# sensor-input.net
KiCad netlist of a schematic drawn in EAGLE
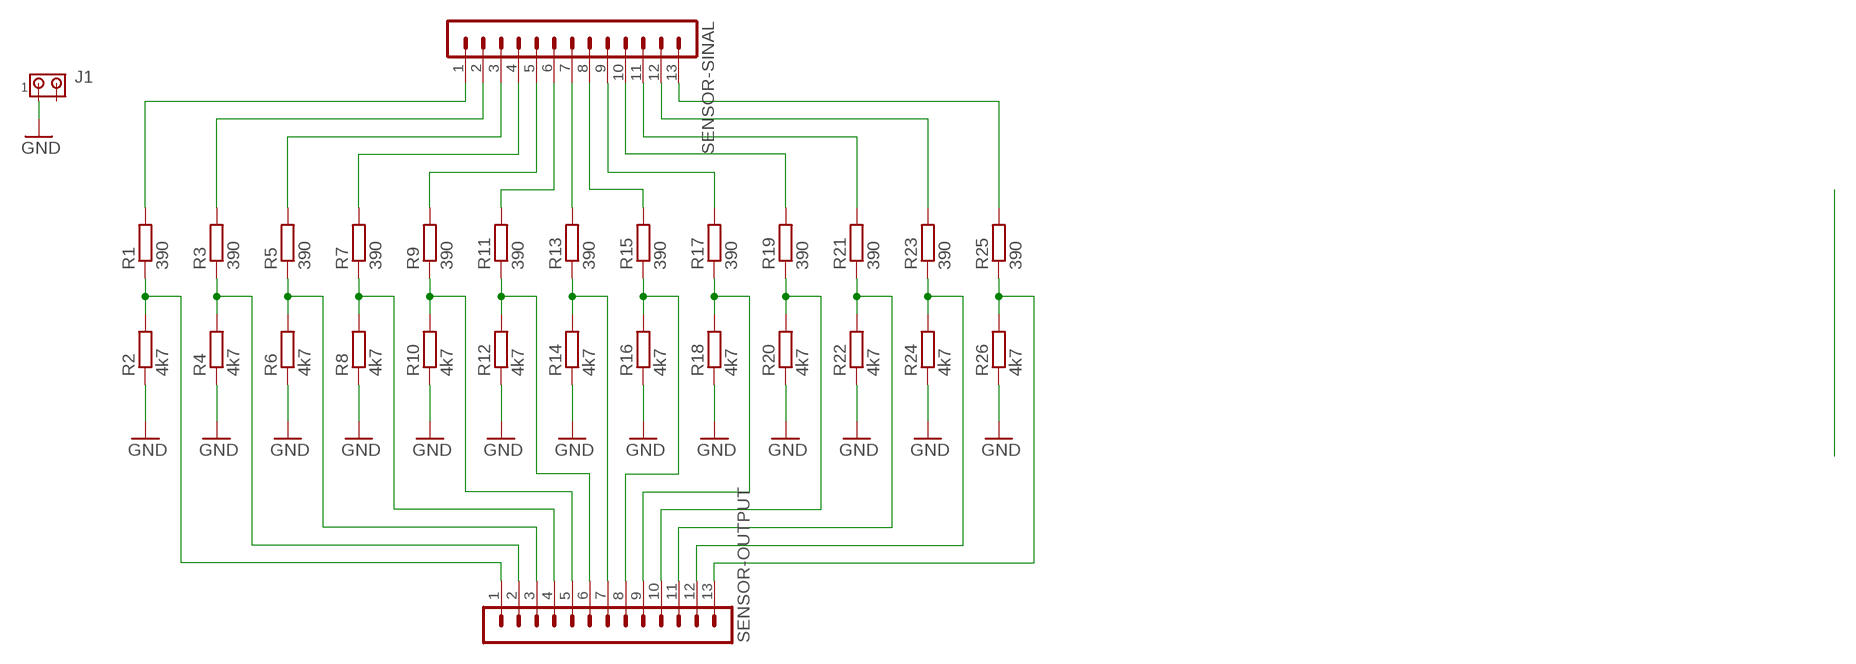
[diagram p0: schematic, sheet 1]

(export (version "E")
  (design (tool "Eeschema 10.0.6"))
  (components
    (comp (ref "J1")
      (value "MTA02-100")
      (footprint "eagle-import:10X02MTA")
      (libsource (lib "eagle-import") (part "MTA02-100"))
    )
    (comp (ref "R1")
      (value "390")
      (footprint "eagle-import:0207_7")
      (libsource (lib "eagle-import") (part "R-EU_0207/7"))
    )
    (comp (ref "R2")
      (value "4k7")
      (footprint "eagle-import:0207_7")
      (libsource (lib "eagle-import") (part "R-EU_0207/7"))
    )
    (comp (ref "R3")
      (value "390")
      (footprint "eagle-import:0207_7")
      (libsource (lib "eagle-import") (part "R-EU_0207/7"))
    )
    (comp (ref "R4")
      (value "4k7")
      (footprint "eagle-import:0207_7")
      (libsource (lib "eagle-import") (part "R-EU_0207/7"))
    )
    (comp (ref "R5")
      (value "390")
      (footprint "eagle-import:0207_7")
      (libsource (lib "eagle-import") (part "R-EU_0207/7"))
    )
    (comp (ref "R6")
      (value "4k7")
      (footprint "eagle-import:0207_7")
      (libsource (lib "eagle-import") (part "R-EU_0207/7"))
    )
    (comp (ref "R7")
      (value "390")
      (footprint "eagle-import:0207_7")
      (libsource (lib "eagle-import") (part "R-EU_0207/7"))
    )
    (comp (ref "R8")
      (value "4k7")
      (footprint "eagle-import:0207_7")
      (libsource (lib "eagle-import") (part "R-EU_0207/7"))
    )
    (comp (ref "R9")
      (value "390")
      (footprint "eagle-import:0207_7")
      (libsource (lib "eagle-import") (part "R-EU_0207/7"))
    )
    (comp (ref "R10")
      (value "4k7")
      (footprint "eagle-import:0207_7")
      (libsource (lib "eagle-import") (part "R-EU_0207/7"))
    )
    (comp (ref "R11")
      (value "390")
      (footprint "eagle-import:0207_7")
      (libsource (lib "eagle-import") (part "R-EU_0207/7"))
    )
    (comp (ref "R12")
      (value "4k7")
      (footprint "eagle-import:0207_7")
      (libsource (lib "eagle-import") (part "R-EU_0207/7"))
    )
    (comp (ref "R13")
      (value "390")
      (footprint "eagle-import:0207_7")
      (libsource (lib "eagle-import") (part "R-EU_0207/7"))
    )
    (comp (ref "R14")
      (value "4k7")
      (footprint "eagle-import:0207_7")
      (libsource (lib "eagle-import") (part "R-EU_0207/7"))
    )
    (comp (ref "R15")
      (value "390")
      (footprint "eagle-import:0207_7")
      (libsource (lib "eagle-import") (part "R-EU_0207/7"))
    )
    (comp (ref "R16")
      (value "4k7")
      (footprint "eagle-import:0207_7")
      (libsource (lib "eagle-import") (part "R-EU_0207/7"))
    )
    (comp (ref "R17")
      (value "390")
      (footprint "eagle-import:0207_7")
      (libsource (lib "eagle-import") (part "R-EU_0207/7"))
    )
    (comp (ref "R18")
      (value "4k7")
      (footprint "eagle-import:0207_7")
      (libsource (lib "eagle-import") (part "R-EU_0207/7"))
    )
    (comp (ref "R19")
      (value "390")
      (footprint "eagle-import:0207_7")
      (libsource (lib "eagle-import") (part "R-EU_0207/7"))
    )
    (comp (ref "R20")
      (value "4k7")
      (footprint "eagle-import:0207_7")
      (libsource (lib "eagle-import") (part "R-EU_0207/7"))
    )
    (comp (ref "R21")
      (value "390")
      (footprint "eagle-import:0207_7")
      (libsource (lib "eagle-import") (part "R-EU_0207/7"))
    )
    (comp (ref "R22")
      (value "4k7")
      (footprint "eagle-import:0207_7")
      (libsource (lib "eagle-import") (part "R-EU_0207/7"))
    )
    (comp (ref "R23")
      (value "390")
      (footprint "eagle-import:0207_7")
      (libsource (lib "eagle-import") (part "R-EU_0207/7"))
    )
    (comp (ref "R24")
      (value "4k7")
      (footprint "eagle-import:0207_7")
      (libsource (lib "eagle-import") (part "R-EU_0207/7"))
    )
    (comp (ref "R25")
      (value "390")
      (footprint "eagle-import:0207_7")
      (libsource (lib "eagle-import") (part "R-EU_0207/7"))
    )
    (comp (ref "R26")
      (value "4k7")
      (footprint "eagle-import:0207_7")
      (libsource (lib "eagle-import") (part "R-EU_0207/7"))
    )
    (comp (ref "SENSOR-OUTPUT")
      (value "MA13-1")
      (footprint "eagle-import:MA13-1")
      (libsource (lib "eagle-import") (part "MA13-1"))
    )
    (comp (ref "SENSOR-SINAL")
      (value "MA13-1")
      (footprint "eagle-import:MA13-1")
      (libsource (lib "eagle-import") (part "MA13-1"))
    )
  )
  (nets
    (net (code "1") (name "GND") (class "Default")
      (node (ref "J1") (pin "1") (pinfunction "1_1") (pintype "passive"))
      (node (ref "R10") (pin "1") (pinfunction "1_1") (pintype "passive"))
      (node (ref "R12") (pin "1") (pinfunction "1_1") (pintype "passive"))
      (node (ref "R14") (pin "1") (pinfunction "1_1") (pintype "passive"))
      (node (ref "R16") (pin "1") (pinfunction "1_1") (pintype "passive"))
      (node (ref "R18") (pin "1") (pinfunction "1_1") (pintype "passive"))
      (node (ref "R2") (pin "1") (pinfunction "1_1") (pintype "passive"))
      (node (ref "R20") (pin "1") (pinfunction "1_1") (pintype "passive"))
      (node (ref "R22") (pin "1") (pinfunction "1_1") (pintype "passive"))
      (node (ref "R24") (pin "1") (pinfunction "1_1") (pintype "passive"))
      (node (ref "R26") (pin "1") (pinfunction "1_1") (pintype "passive"))
      (node (ref "R4") (pin "1") (pinfunction "1_1") (pintype "passive"))
      (node (ref "R6") (pin "1") (pinfunction "1_1") (pintype "passive"))
      (node (ref "R8") (pin "1") (pinfunction "1_1") (pintype "passive"))
    )
    (net (code "2") (name "Net-(R1-Pad1)") (class "Default")
      (node (ref "R1") (pin "1") (pinfunction "1_1") (pintype "passive"))
      (node (ref "R2") (pin "2") (pinfunction "2_2") (pintype "passive"))
      (node (ref "SENSOR-OUTPUT") (pin "1") (pinfunction "1_1") (pintype "passive"))
    )
    (net (code "3") (name "Net-(R1-Pad2)") (class "Default")
      (node (ref "R1") (pin "2") (pinfunction "2_2") (pintype "passive"))
      (node (ref "SENSOR-SINAL") (pin "1") (pinfunction "1_1") (pintype "passive"))
    )
    (net (code "4") (name "Net-(R3-Pad1)") (class "Default")
      (node (ref "R3") (pin "1") (pinfunction "1_1") (pintype "passive"))
      (node (ref "R4") (pin "2") (pinfunction "2_2") (pintype "passive"))
      (node (ref "SENSOR-OUTPUT") (pin "2") (pinfunction "2_2") (pintype "passive"))
    )
    (net (code "5") (name "Net-(R3-Pad2)") (class "Default")
      (node (ref "R3") (pin "2") (pinfunction "2_2") (pintype "passive"))
      (node (ref "SENSOR-SINAL") (pin "2") (pinfunction "2_2") (pintype "passive"))
    )
    (net (code "6") (name "Net-(R5-Pad1)") (class "Default")
      (node (ref "R5") (pin "1") (pinfunction "1_1") (pintype "passive"))
      (node (ref "R6") (pin "2") (pinfunction "2_2") (pintype "passive"))
      (node (ref "SENSOR-OUTPUT") (pin "3") (pinfunction "3_3") (pintype "passive"))
    )
    (net (code "7") (name "Net-(R5-Pad2)") (class "Default")
      (node (ref "R5") (pin "2") (pinfunction "2_2") (pintype "passive"))
      (node (ref "SENSOR-SINAL") (pin "3") (pinfunction "3_3") (pintype "passive"))
    )
    (net (code "8") (name "Net-(R7-Pad1)") (class "Default")
      (node (ref "R7") (pin "1") (pinfunction "1_1") (pintype "passive"))
      (node (ref "R8") (pin "2") (pinfunction "2_2") (pintype "passive"))
      (node (ref "SENSOR-OUTPUT") (pin "4") (pinfunction "4_4") (pintype "passive"))
    )
    (net (code "9") (name "Net-(R7-Pad2)") (class "Default")
      (node (ref "R7") (pin "2") (pinfunction "2_2") (pintype "passive"))
      (node (ref "SENSOR-SINAL") (pin "4") (pinfunction "4_4") (pintype "passive"))
    )
    (net (code "10") (name "Net-(R9-Pad2)") (class "Default")
      (node (ref "R9") (pin "2") (pinfunction "2_2") (pintype "passive"))
      (node (ref "SENSOR-SINAL") (pin "5") (pinfunction "5_5") (pintype "passive"))
    )
    (net (code "11") (name "Net-(R10-Pad2)") (class "Default")
      (node (ref "R10") (pin "2") (pinfunction "2_2") (pintype "passive"))
      (node (ref "R9") (pin "1") (pinfunction "1_1") (pintype "passive"))
      (node (ref "SENSOR-OUTPUT") (pin "5") (pinfunction "5_5") (pintype "passive"))
    )
    (net (code "12") (name "Net-(R11-Pad1)") (class "Default")
      (node (ref "R11") (pin "1") (pinfunction "1_1") (pintype "passive"))
      (node (ref "R12") (pin "2") (pinfunction "2_2") (pintype "passive"))
      (node (ref "SENSOR-OUTPUT") (pin "6") (pinfunction "6_6") (pintype "passive"))
    )
    (net (code "13") (name "Net-(R11-Pad2)") (class "Default")
      (node (ref "R11") (pin "2") (pinfunction "2_2") (pintype "passive"))
      (node (ref "SENSOR-SINAL") (pin "6") (pinfunction "6_6") (pintype "passive"))
    )
    (net (code "14") (name "Net-(R13-Pad1)") (class "Default")
      (node (ref "R13") (pin "1") (pinfunction "1_1") (pintype "passive"))
      (node (ref "R14") (pin "2") (pinfunction "2_2") (pintype "passive"))
      (node (ref "SENSOR-OUTPUT") (pin "7") (pinfunction "7_7") (pintype "passive"))
    )
    (net (code "15") (name "Net-(R13-Pad2)") (class "Default")
      (node (ref "R13") (pin "2") (pinfunction "2_2") (pintype "passive"))
      (node (ref "SENSOR-SINAL") (pin "7") (pinfunction "7_7") (pintype "passive"))
    )
    (net (code "16") (name "Net-(R15-Pad1)") (class "Default")
      (node (ref "R15") (pin "1") (pinfunction "1_1") (pintype "passive"))
      (node (ref "R16") (pin "2") (pinfunction "2_2") (pintype "passive"))
      (node (ref "SENSOR-OUTPUT") (pin "8") (pinfunction "8_8") (pintype "passive"))
    )
    (net (code "17") (name "Net-(R15-Pad2)") (class "Default")
      (node (ref "R15") (pin "2") (pinfunction "2_2") (pintype "passive"))
      (node (ref "SENSOR-SINAL") (pin "8") (pinfunction "8_8") (pintype "passive"))
    )
    (net (code "18") (name "Net-(R17-Pad1)") (class "Default")
      (node (ref "R17") (pin "1") (pinfunction "1_1") (pintype "passive"))
      (node (ref "R18") (pin "2") (pinfunction "2_2") (pintype "passive"))
      (node (ref "SENSOR-OUTPUT") (pin "9") (pinfunction "9_9") (pintype "passive"))
    )
    (net (code "19") (name "Net-(R17-Pad2)") (class "Default")
      (node (ref "R17") (pin "2") (pinfunction "2_2") (pintype "passive"))
      (node (ref "SENSOR-SINAL") (pin "9") (pinfunction "9_9") (pintype "passive"))
    )
    (net (code "20") (name "Net-(R19-Pad1)") (class "Default")
      (node (ref "R19") (pin "1") (pinfunction "1_1") (pintype "passive"))
      (node (ref "R20") (pin "2") (pinfunction "2_2") (pintype "passive"))
      (node (ref "SENSOR-OUTPUT") (pin "10") (pinfunction "10_10") (pintype "passive"))
    )
    (net (code "21") (name "Net-(R19-Pad2)") (class "Default")
      (node (ref "R19") (pin "2") (pinfunction "2_2") (pintype "passive"))
      (node (ref "SENSOR-SINAL") (pin "10") (pinfunction "10_10") (pintype "passive"))
    )
    (net (code "22") (name "Net-(R21-Pad1)") (class "Default")
      (node (ref "R21") (pin "1") (pinfunction "1_1") (pintype "passive"))
      (node (ref "R22") (pin "2") (pinfunction "2_2") (pintype "passive"))
      (node (ref "SENSOR-OUTPUT") (pin "11") (pinfunction "11_11") (pintype "passive"))
    )
    (net (code "23") (name "Net-(R21-Pad2)") (class "Default")
      (node (ref "R21") (pin "2") (pinfunction "2_2") (pintype "passive"))
      (node (ref "SENSOR-SINAL") (pin "11") (pinfunction "11_11") (pintype "passive"))
    )
    (net (code "24") (name "Net-(R23-Pad1)") (class "Default")
      (node (ref "R23") (pin "1") (pinfunction "1_1") (pintype "passive"))
      (node (ref "R24") (pin "2") (pinfunction "2_2") (pintype "passive"))
      (node (ref "SENSOR-OUTPUT") (pin "12") (pinfunction "12_12") (pintype "passive"))
    )
    (net (code "25") (name "Net-(R23-Pad2)") (class "Default")
      (node (ref "R23") (pin "2") (pinfunction "2_2") (pintype "passive"))
      (node (ref "SENSOR-SINAL") (pin "12") (pinfunction "12_12") (pintype "passive"))
    )
    (net (code "26") (name "Net-(R25-Pad1)") (class "Default")
      (node (ref "R25") (pin "1") (pinfunction "1_1") (pintype "passive"))
      (node (ref "R26") (pin "2") (pinfunction "2_2") (pintype "passive"))
      (node (ref "SENSOR-OUTPUT") (pin "13") (pinfunction "13_13") (pintype "passive"))
    )
    (net (code "27") (name "Net-(R25-Pad2)") (class "Default")
      (node (ref "R25") (pin "2") (pinfunction "2_2") (pintype "passive"))
      (node (ref "SENSOR-SINAL") (pin "13") (pinfunction "13_13") (pintype "passive"))
    )
    (net (code "28") (name "unconnected-(J1-Pad2)") (class "Default")
      (node (ref "J1") (pin "2") (pinfunction "2_2") (pintype "passive"))
    )
  )
)
